# AMU_type_2_v1.net
KiCad netlist of a schematic drawn in Altium Designer
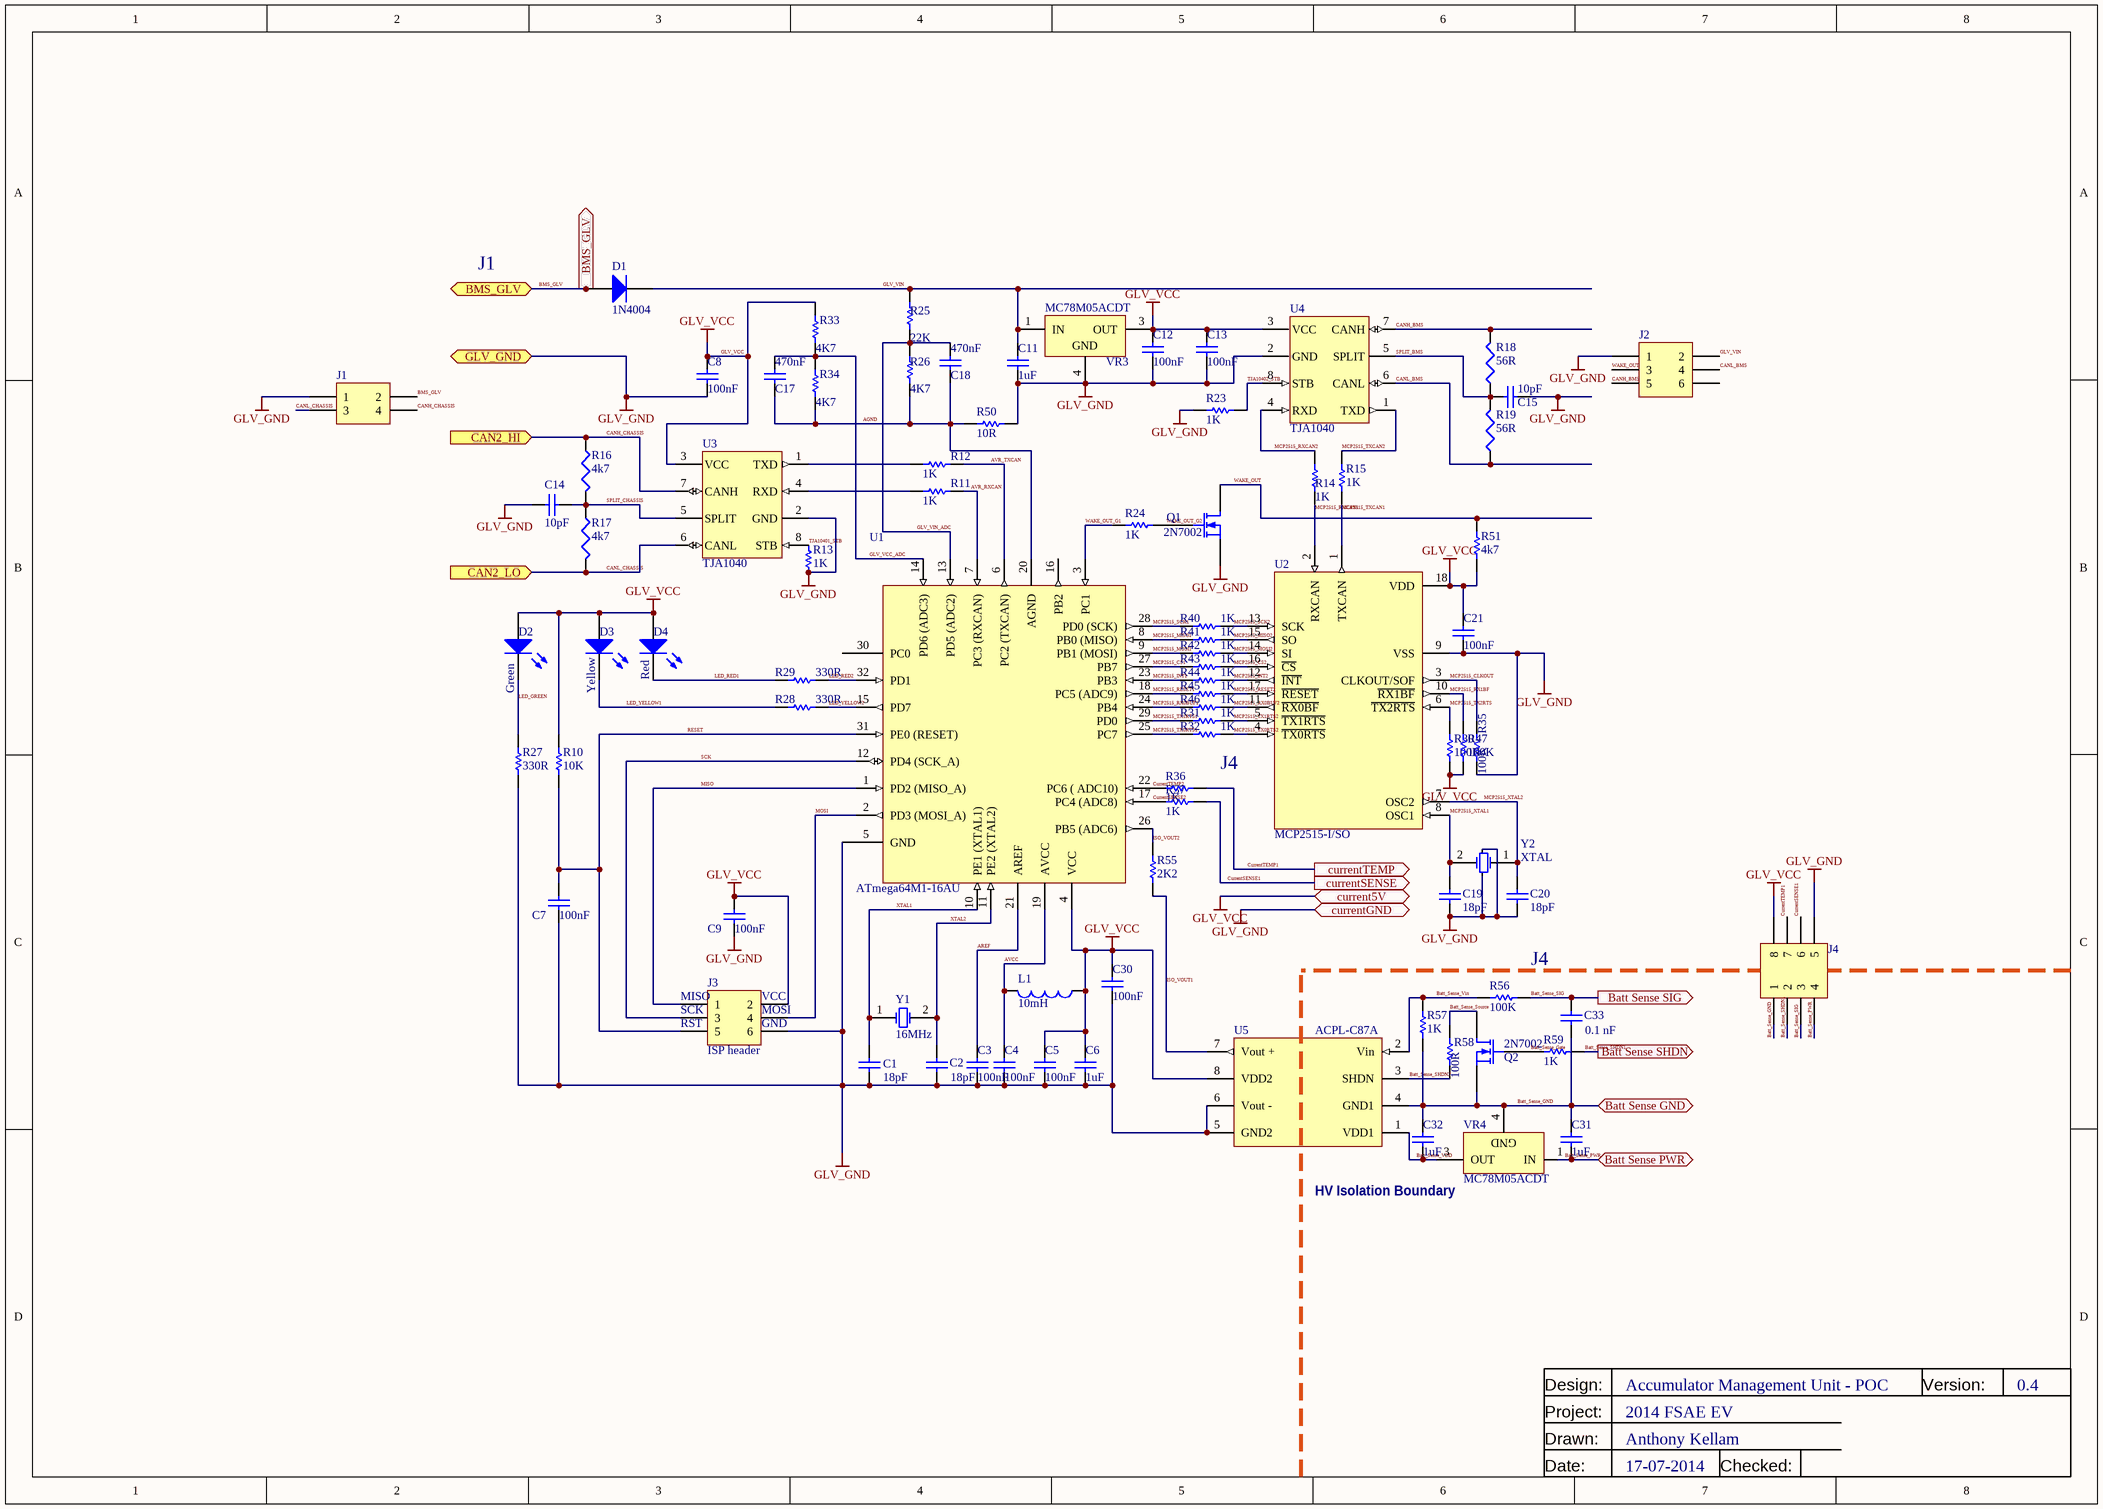
[diagram p0: AMU_type_2_v1.SchDoc]

(export (version "E")
  (design (tool "Eeschema 10.0.6"))
  (components
    (comp (ref "C1")
      (value "18pF")
      (footprint "0603C")
      (description "Capacitor (Semiconductor SIM Model)")
      (fields (field (name "Comment") "Cap Semi") (field (name "PUBLISHER") "Altium Limited"))
      (libsource (lib "Miscellaneous Devices") (part "Cap Semi"))
    )
    (comp (ref "C2")
      (value "18pF")
      (footprint "0603C")
      (description "Capacitor (Semiconductor SIM Model)")
      (fields (field (name "Comment") "Cap Semi") (field (name "PUBLISHER") "Altium Limited"))
      (libsource (lib "Miscellaneous Devices") (part "Cap Semi"))
    )
    (comp (ref "C3")
      (value "100nF")
      (footprint "0603C")
      (description "Capacitor (Semiconductor SIM Model)")
      (fields (field (name "Comment") "Cap Semi") (field (name "PUBLISHER") "Altium Limited"))
      (libsource (lib "Miscellaneous Devices") (part "Cap Semi"))
    )
    (comp (ref "C4")
      (value "100nF")
      (footprint "0603C")
      (description "Capacitor (Semiconductor SIM Model)")
      (fields (field (name "Comment") "Cap Semi") (field (name "PUBLISHER") "Altium Limited"))
      (libsource (lib "Miscellaneous Devices") (part "Cap Semi"))
    )
    (comp (ref "C5")
      (value "100nF")
      (footprint "0603C")
      (description "Capacitor (Semiconductor SIM Model)")
      (fields (field (name "Comment") "Cap Semi") (field (name "PUBLISHER") "Altium Limited"))
      (libsource (lib "Miscellaneous Devices") (part "Cap Semi"))
    )
    (comp (ref "C6")
      (value "1uF")
      (footprint "0603C")
      (description "Capacitor (Semiconductor SIM Model)")
      (fields (field (name "Comment") "Cap Semi") (field (name "PUBLISHER") "Altium Limited"))
      (libsource (lib "Miscellaneous Devices") (part "Cap Semi"))
    )
    (comp (ref "C7")
      (value "100nF")
      (footprint "0603C")
      (description "Capacitor (Semiconductor SIM Model)")
      (fields (field (name "Comment") "Cap Semi") (field (name "PUBLISHER") "Altium Limited"))
      (libsource (lib "Miscellaneous Devices") (part "Cap Semi"))
    )
    (comp (ref "C8")
      (value "100nF")
      (footprint "0603C")
      (description "Capacitor (Semiconductor SIM Model)")
      (fields (field (name "Comment") "Cap Semi") (field (name "PUBLISHER") "Altium Limited"))
      (libsource (lib "Miscellaneous Devices") (part "Cap Semi"))
    )
    (comp (ref "C9")
      (value "100nF")
      (footprint "0603C")
      (description "Capacitor (Semiconductor SIM Model)")
      (fields (field (name "Comment") "Cap Semi") (field (name "PUBLISHER") "Altium Limited"))
      (libsource (lib "Miscellaneous Devices") (part "Cap Semi"))
    )
    (comp (ref "C11")
      (value "1uF")
      (footprint "0603C")
      (description "Capacitor (Semiconductor SIM Model)")
      (fields (field (name "Comment") "Cap Semi") (field (name "PUBLISHER") "Altium Limited"))
      (libsource (lib "Miscellaneous Devices") (part "Cap Semi"))
    )
    (comp (ref "C12")
      (value "100nF")
      (footprint "0603C")
      (description "Capacitor (Semiconductor SIM Model)")
      (fields (field (name "Comment") "Cap Semi") (field (name "PUBLISHER") "Altium Limited"))
      (libsource (lib "Miscellaneous Devices") (part "Cap Semi"))
    )
    (comp (ref "C13")
      (value "100nF")
      (footprint "0603C")
      (description "Capacitor (Semiconductor SIM Model)")
      (fields (field (name "Comment") "Cap Semi") (field (name "PUBLISHER") "Altium Limited"))
      (libsource (lib "Miscellaneous Devices") (part "Cap Semi"))
    )
    (comp (ref "C14")
      (value "10pF")
      (footprint "0603C")
      (description "Capacitor (Semiconductor SIM Model)")
      (fields (field (name "Comment") "Cap Semi") (field (name "PUBLISHER") "Altium Limited"))
      (libsource (lib "Miscellaneous Devices") (part "Cap Semi"))
    )
    (comp (ref "C15")
      (value "10pF")
      (footprint "0603C")
      (description "Capacitor (Semiconductor SIM Model)")
      (fields (field (name "Comment") "Cap Semi") (field (name "PUBLISHER") "Altium Limited"))
      (libsource (lib "Miscellaneous Devices") (part "Cap Semi"))
    )
    (comp (ref "C17")
      (value "470nF")
      (footprint "0603C")
      (description "Capacitor (Semiconductor SIM Model)")
      (fields (field (name "Comment") "Cap Semi") (field (name "PUBLISHER") "Altium Limited"))
      (libsource (lib "Miscellaneous Devices") (part "Cap Semi"))
    )
    (comp (ref "C18")
      (value "470nF")
      (footprint "0603C")
      (description "Capacitor (Semiconductor SIM Model)")
      (fields (field (name "Comment") "Cap Semi") (field (name "PUBLISHER") "Altium Limited"))
      (libsource (lib "Miscellaneous Devices") (part "Cap Semi"))
    )
    (comp (ref "C19")
      (value "18pF")
      (footprint "0603C")
      (description "Capacitor (Semiconductor SIM Model)")
      (fields (field (name "Comment") "Cap Semi") (field (name "PUBLISHER") "Altium Limited"))
      (libsource (lib "Miscellaneous Devices") (part "Cap Semi"))
    )
    (comp (ref "C20")
      (value "18pF")
      (footprint "0603C")
      (description "Capacitor (Semiconductor SIM Model)")
      (fields (field (name "Comment") "Cap Semi") (field (name "PUBLISHER") "Altium Limited"))
      (libsource (lib "Miscellaneous Devices") (part "Cap Semi"))
    )
    (comp (ref "C21")
      (value "100nF")
      (footprint "0603C")
      (description "Capacitor (Semiconductor SIM Model)")
      (fields (field (name "Comment") "Cap Semi") (field (name "PUBLISHER") "Altium Limited"))
      (libsource (lib "Miscellaneous Devices") (part "Cap Semi"))
    )
    (comp (ref "C30")
      (value "100nF")
      (footprint "0603C")
      (description "Capacitor (Semiconductor SIM Model)")
      (fields (field (name "Comment") "Cap Semi") (field (name "PUBLISHER") "Altium Limited"))
      (libsource (lib "Miscellaneous Devices") (part "Cap Semi"))
    )
    (comp (ref "C31")
      (value "1uF")
      (footprint "0603C")
      (description "Capacitor (Semiconductor SIM Model)")
      (fields (field (name "Comment") "Cap Semi") (field (name "PUBLISHER") "Altium Limited"))
      (libsource (lib "Miscellaneous Devices") (part "Cap Semi"))
    )
    (comp (ref "C32")
      (value "1uF")
      (footprint "0603C")
      (description "Capacitor (Semiconductor SIM Model)")
      (fields (field (name "Comment") "Cap Semi") (field (name "PUBLISHER") "Altium Limited"))
      (libsource (lib "Miscellaneous Devices") (part "Cap Semi"))
    )
    (comp (ref "C33")
      (value "0.1 nF")
      (footprint "0603C")
      (description "Capacitor (Semiconductor SIM Model)")
      (fields (field (name "Comment") "Cap Semi") (field (name "PUBLISHER") "Altium Limited"))
      (libsource (lib "Miscellaneous Devices") (part "Cap Semi"))
    )
    (comp (ref "D1")
      (value "1N4004")
      (footprint "DO-214AC")
      (description "Default Diode")
      (fields (field (name "PUBLISHER") "Altium Limited"))
      (libsource (lib "Miscellaneous Devices") (part "Diode"))
    )
    (comp (ref "D2")
      (value "Green")
      (footprint "2012[0805]_LED")
      (description "Typical RED, GREEN, YELLOW, AMBER GaAs LED")
      (fields (field (name "PUBLISHER") "Altium Limited"))
      (libsource (lib "Miscellaneous Devices") (part "LED2"))
    )
    (comp (ref "D3")
      (value "Yellow")
      (footprint "2012[0805]_LED")
      (description "Typical RED, GREEN, YELLOW, AMBER GaAs LED")
      (fields (field (name "PUBLISHER") "Altium Limited"))
      (libsource (lib "Miscellaneous Devices") (part "LED2"))
    )
    (comp (ref "D4")
      (value "Red")
      (footprint "2012[0805]_LED")
      (description "Typical RED, GREEN, YELLOW, AMBER GaAs LED")
      (fields (field (name "PUBLISHER") "Altium Limited"))
      (libsource (lib "Miscellaneous Devices") (part "LED2"))
    )
    (comp (ref "J1")
      (value "Header 2X2")
      (footprint "Molex 4 Pin")
      (description "Header, 2-Pin, Dual row")
      (fields (field (name "PUBLISHER") "Altium Limited"))
      (libsource (lib "Miscellaneous Connectors") (part "Header 2X2"))
    )
    (comp (ref "J2")
      (value "Header 3X2")
      (footprint "Molex 6 Pin")
      (description "Header, 3-Pin, Dual row")
      (fields (field (name "PUBLISHER") "Altium Limited"))
      (libsource (lib "Miscellaneous Connectors") (part "Header 3X2"))
    )
    (comp (ref "J3")
      (value "ISP header")
      (footprint "ISP Header")
      (description "Header, 3-Pin, Dual row")
      (fields (field (name "PUBLISHER") "Altium Limited"))
      (libsource (lib "Miscellaneous Connectors") (part "Header 3X2"))
    )
    (comp (ref "J4")
      (value "Header 4X2")
      (footprint "MOLEX_8")
      (description "Header, 4-Pin, Dual row")
      (fields (field (name "PUBLISHER") "Altium Limited"))
      (libsource (lib "Miscellaneous Connectors") (part "Header 4X2"))
    )
    (comp (ref "L1")
      (value "10mH")
      (footprint "2012[0805]_IND")
      (description "Inductor")
      (fields (field (name "PUBLISHER") "Altium Limited"))
      (libsource (lib "Miscellaneous Devices") (part "Inductor"))
    )
    (comp (ref "Q1")
      (value "2N7002")
      (footprint "SOT23A")
      (description "N-Channel MOSFET")
      (fields
        (field (name "MANUFACTURER") "NXP Semiconductors")
        (field (name "MANUFACTURER PART NUMBER") "2N7002P,215")
        (field (name "PUBLISHER") "Altium Limited")
      )
      (libsource (lib "Miscellaneous Devices") (part "MOSFET-N"))
    )
    (comp (ref "Q2")
      (value "2N7002")
      (footprint "SOT23A")
      (description "N-Channel MOSFET")
      (fields (field (name "PUBLISHER") "Altium Limited"))
      (libsource (lib "") (part "MOSFET-N_1"))
    )
    (comp (ref "R10")
      (value "10K")
      (footprint "2012[0805]_Res")
      (description "Resistor")
      (fields (field (name "Comment") "Res1") (field (name "PUBLISHER") "Altium Limited"))
      (libsource (lib "Miscellaneous Devices") (part "Res1"))
    )
    (comp (ref "R11")
      (value "1K")
      (footprint "2012[0805]_Res")
      (description "Resistor")
      (fields (field (name "Comment") "Res1") (field (name "PUBLISHER") "Altium Limited"))
      (libsource (lib "Miscellaneous Devices") (part "Res1"))
    )
    (comp (ref "R12")
      (value "1K")
      (footprint "2012[0805]_Res")
      (description "Resistor")
      (fields (field (name "Comment") "Res1") (field (name "PUBLISHER") "Altium Limited"))
      (libsource (lib "Miscellaneous Devices") (part "Res1"))
    )
    (comp (ref "R13")
      (value "1K")
      (footprint "2012[0805]_Res")
      (description "Resistor")
      (fields (field (name "Comment") "Res1") (field (name "PUBLISHER") "Altium Limited"))
      (libsource (lib "") (part "Res1_1"))
    )
    (comp (ref "R14")
      (value "1K")
      (footprint "2012[0805]_Res")
      (description "Resistor")
      (fields (field (name "Comment") "Res1") (field (name "PUBLISHER") "Altium Limited"))
      (libsource (lib "Miscellaneous Devices") (part "Res1"))
    )
    (comp (ref "R15")
      (value "1K")
      (footprint "2012[0805]_Res")
      (description "Resistor")
      (fields (field (name "Comment") "Res1") (field (name "PUBLISHER") "Altium Limited"))
      (libsource (lib "Miscellaneous Devices") (part "Res1"))
    )
    (comp (ref "R16")
      (value "4k7")
      (footprint "2012[0805]_Res")
      (description "Resistor")
      (fields (field (name "Comment") "Res3") (field (name "PUBLISHER") "Altium Limited"))
      (libsource (lib "Miscellaneous Devices") (part "Res3"))
    )
    (comp (ref "R17")
      (value "4k7")
      (footprint "2012[0805]_Res")
      (description "Resistor")
      (fields (field (name "Comment") "Res3") (field (name "PUBLISHER") "Altium Limited"))
      (libsource (lib "Miscellaneous Devices") (part "Res3"))
    )
    (comp (ref "R18")
      (value "56R")
      (footprint "2012[0805]_Res")
      (description "Resistor")
      (fields (field (name "Comment") "Res3") (field (name "PUBLISHER") "Altium Limited"))
      (libsource (lib "Miscellaneous Devices") (part "Res3"))
    )
    (comp (ref "R19")
      (value "56R")
      (footprint "2012[0805]_Res")
      (description "Resistor")
      (fields (field (name "Comment") "Res3") (field (name "PUBLISHER") "Altium Limited"))
      (libsource (lib "Miscellaneous Devices") (part "Res3"))
    )
    (comp (ref "R23")
      (value "1K")
      (footprint "2012[0805]_Res")
      (description "Resistor")
      (fields (field (name "Comment") "Res1") (field (name "PUBLISHER") "Altium Limited"))
      (libsource (lib "Miscellaneous Devices") (part "Res1"))
    )
    (comp (ref "R24")
      (value "1K")
      (footprint "2012[0805]_Res")
      (description "Resistor")
      (fields (field (name "Comment") "Res1") (field (name "PUBLISHER") "Altium Limited"))
      (libsource (lib "Miscellaneous Devices") (part "Res1"))
    )
    (comp (ref "R25")
      (value "22K")
      (footprint "2012[0805]_Res")
      (description "Resistor")
      (fields (field (name "Comment") "Res1") (field (name "PUBLISHER") "Altium Limited"))
      (libsource (lib "Miscellaneous Devices") (part "Res1"))
    )
    (comp (ref "R26")
      (value "4K7")
      (footprint "2012[0805]_Res")
      (description "Resistor")
      (fields (field (name "Comment") "Res1") (field (name "PUBLISHER") "Altium Limited"))
      (libsource (lib "Miscellaneous Devices") (part "Res1"))
    )
    (comp (ref "R27")
      (value "330R")
      (footprint "2012[0805]_Res")
      (description "Resistor")
      (fields (field (name "Comment") "Res1") (field (name "PUBLISHER") "Altium Limited"))
      (libsource (lib "Miscellaneous Devices") (part "Res1"))
    )
    (comp (ref "R28")
      (value "330R")
      (footprint "2012[0805]_Res")
      (description "Resistor")
      (fields (field (name "Comment") "Res1") (field (name "PUBLISHER") "Altium Limited"))
      (libsource (lib "Miscellaneous Devices") (part "Res1"))
    )
    (comp (ref "R29")
      (value "330R")
      (footprint "2012[0805]_Res")
      (description "Resistor")
      (fields (field (name "Comment") "Res1") (field (name "PUBLISHER") "Altium Limited"))
      (libsource (lib "Miscellaneous Devices") (part "Res1"))
    )
    (comp (ref "R30")
      (value "100K")
      (footprint "2012[0805]_Res")
      (description "Resistor")
      (fields (field (name "Comment") "Res1") (field (name "PUBLISHER") "Altium Limited"))
      (libsource (lib "Miscellaneous Devices") (part "Res1"))
    )
    (comp (ref "R31")
      (value "1K")
      (footprint "2012[0805]_Res")
      (description "Resistor")
      (fields (field (name "Comment") "Res1") (field (name "PUBLISHER") "Altium Limited"))
      (libsource (lib "Miscellaneous Devices") (part "Res1"))
    )
    (comp (ref "R32")
      (value "1K")
      (footprint "2012[0805]_Res")
      (description "Resistor")
      (fields (field (name "Comment") "Res1") (field (name "PUBLISHER") "Altium Limited"))
      (libsource (lib "Miscellaneous Devices") (part "Res1"))
    )
    (comp (ref "R33")
      (value "4K7")
      (footprint "2012[0805]_Res")
      (description "Resistor")
      (fields (field (name "Comment") "Res1") (field (name "PUBLISHER") "Altium Limited"))
      (libsource (lib "Miscellaneous Devices") (part "Res1"))
    )
    (comp (ref "R34")
      (value "4K7")
      (footprint "2012[0805]_Res")
      (description "Resistor")
      (fields (field (name "Comment") "Res1") (field (name "PUBLISHER") "Altium Limited"))
      (libsource (lib "Miscellaneous Devices") (part "Res1"))
    )
    (comp (ref "R35")
      (value "100K")
      (footprint "2012[0805]_Res")
      (description "Resistor")
      (fields (field (name "Comment") "Res1") (field (name "PUBLISHER") "Altium Limited"))
      (libsource (lib "Miscellaneous Devices") (part "Res1"))
    )
    (comp (ref "R36")
      (value "1K")
      (footprint "2012[0805]_Res")
      (description "Resistor")
      (fields (field (name "Comment") "Res1") (field (name "PUBLISHER") "Altium Limited"))
      (libsource (lib "Miscellaneous Devices") (part "Res1"))
    )
    (comp (ref "R37")
      (value "1K")
      (footprint "2012[0805]_Res")
      (description "Resistor")
      (fields (field (name "Comment") "Res1") (field (name "PUBLISHER") "Altium Limited"))
      (libsource (lib "Miscellaneous Devices") (part "Res1"))
    )
    (comp (ref "R40")
      (value "1K")
      (footprint "2012[0805]_Res")
      (description "Resistor")
      (fields (field (name "Comment") "Res1") (field (name "PUBLISHER") "Altium Limited"))
      (libsource (lib "Miscellaneous Devices") (part "Res1"))
    )
    (comp (ref "R41")
      (value "1K")
      (footprint "2012[0805]_Res")
      (description "Resistor")
      (fields (field (name "Comment") "Res1") (field (name "PUBLISHER") "Altium Limited"))
      (libsource (lib "Miscellaneous Devices") (part "Res1"))
    )
    (comp (ref "R42")
      (value "1K")
      (footprint "2012[0805]_Res")
      (description "Resistor")
      (fields (field (name "Comment") "Res1") (field (name "PUBLISHER") "Altium Limited"))
      (libsource (lib "Miscellaneous Devices") (part "Res1"))
    )
    (comp (ref "R43")
      (value "1K")
      (footprint "2012[0805]_Res")
      (description "Resistor")
      (fields (field (name "Comment") "Res1") (field (name "PUBLISHER") "Altium Limited"))
      (libsource (lib "Miscellaneous Devices") (part "Res1"))
    )
    (comp (ref "R44")
      (value "1K")
      (footprint "2012[0805]_Res")
      (description "Resistor")
      (fields (field (name "Comment") "Res1") (field (name "PUBLISHER") "Altium Limited"))
      (libsource (lib "Miscellaneous Devices") (part "Res1"))
    )
    (comp (ref "R45")
      (value "1K")
      (footprint "2012[0805]_Res")
      (description "Resistor")
      (fields (field (name "Comment") "Res1") (field (name "PUBLISHER") "Altium Limited"))
      (libsource (lib "Miscellaneous Devices") (part "Res1"))
    )
    (comp (ref "R46")
      (value "1K")
      (footprint "2012[0805]_Res")
      (description "Resistor")
      (fields (field (name "Comment") "Res1") (field (name "PUBLISHER") "Altium Limited"))
      (libsource (lib "Miscellaneous Devices") (part "Res1"))
    )
    (comp (ref "R47")
      (value "100K")
      (footprint "2012[0805]_Res")
      (description "Resistor")
      (fields (field (name "Comment") "Res1") (field (name "PUBLISHER") "Altium Limited"))
      (libsource (lib "Miscellaneous Devices") (part "Res1"))
    )
    (comp (ref "R50")
      (value "10R")
      (footprint "2012[0805]_Res")
      (description "Resistor")
      (fields (field (name "Comment") "Res1") (field (name "PUBLISHER") "Altium Limited"))
      (libsource (lib "Miscellaneous Devices") (part "Res1"))
    )
    (comp (ref "R51")
      (value "4k7")
      (footprint "2012[0805]_Res")
      (description "Resistor")
      (fields (field (name "Comment") "Res1") (field (name "PUBLISHER") "Altium Limited"))
      (libsource (lib "Miscellaneous Devices") (part "Res1"))
    )
    (comp (ref "R55")
      (value "2K2")
      (footprint "2012[0805]_Res")
      (description "Resistor")
      (fields (field (name "Comment") "Res1") (field (name "PUBLISHER") "Altium Limited"))
      (libsource (lib "Miscellaneous Devices") (part "Res1"))
    )
    (comp (ref "R56")
      (value "100K")
      (footprint "2012[0805]_Res")
      (description "Resistor")
      (fields (field (name "Comment") "Res1") (field (name "PUBLISHER") "Altium Limited"))
      (libsource (lib "Miscellaneous Devices") (part "Res1"))
    )
    (comp (ref "R57")
      (value "1K")
      (footprint "2012[0805]_Res")
      (description "Resistor")
      (fields (field (name "Comment") "Res1") (field (name "PUBLISHER") "Altium Limited"))
      (libsource (lib "Miscellaneous Devices") (part "Res1"))
    )
    (comp (ref "R58")
      (value "100R")
      (footprint "2012[0805]_Res")
      (description "Resistor")
      (fields (field (name "Comment") "Res1") (field (name "PUBLISHER") "Altium Limited"))
      (libsource (lib "Miscellaneous Devices") (part "Res1"))
    )
    (comp (ref "R59")
      (value "1K")
      (footprint "2012[0805]_Res")
      (description "Resistor")
      (fields (field (name "Comment") "Res1") (field (name "PUBLISHER") "Altium Limited"))
      (libsource (lib "Miscellaneous Devices") (part "Res1"))
    )
    (comp (ref "U1")
      (value "ATmega64M1-16AU")
      (footprint "32A_L")
      (description "8-Bit AVR Microcontroller with 8K Bytes of In-System Programmable Flash Memory")
      (fields (field (name "PUBLISHER") "Altium Limited"))
      (libsource (lib "Atmel Microcontroller 8-Bit AVR") (part "ATmega8-16AC"))
    )
    (comp (ref "U2")
      (value "MCP2515-I/SO")
      (footprint "SOIC-SO18_N")
      (description "Stand-Alone CAN Controller With SPI Interface, 18-Pin SOIC, Industrial Temperature")
      (fields (field (name "PUBLISHER") "Altium Limited"))
      (libsource (lib "Microchip Interface") (part "MCP2515-I/SO"))
    )
    (comp (ref "U3")
      (value "TJA1040")
      (footprint "Miscellaneous Devices:SO8_L")
      (libsource (lib "Schlib1") (part "TJA1040"))
    )
    (comp (ref "U4")
      (value "TJA1040")
      (footprint "Miscellaneous Devices:SO8_L")
      (libsource (lib "") (part "TJA1040_1"))
    )
    (comp (ref "U5")
      (value "ACPL-C87A")
      (footprint "8S2_L")
      (description "Isolated CAN transceiver")
      (fields (field (name "PUBLISHER") "Altium Limited"))
      (libsource (lib "Atmel Microcontroller 8-Bit AVR") (part "AT90S2343-10SI"))
    )
    (comp (ref "VR3")
      (value "MC78M05ACDT")
      (footprint "369A-13")
      (description "Three-Terminal Medium Current Positive Voltage Regulator")
      (fields (field (name "PUBLISHER") "Altium Limited"))
      (libsource (lib "ON Semi Power Mgt Voltage Regulator") (part "MC78M05ACDT"))
    )
    (comp (ref "VR4")
      (value "MC78M05ACDT")
      (footprint "369A-13")
      (description "Three-Terminal Medium Current Positive Voltage Regulator")
      (fields (field (name "PUBLISHER") "Altium Limited"))
      (libsource (lib "") (part "MC78M05ACDT_1"))
    )
    (comp (ref "Y1")
      (value "16MHz")
      (footprint "Crystal")
      (description "Crystal Oscillator")
      (fields (field (name "PUBLISHER") "Altium Limited"))
      (libsource (lib "Miscellaneous Devices") (part "XTAL"))
    )
    (comp (ref "Y2")
      (value "XTAL")
      (footprint "MCP2515_XTAL")
      (description "Crystal Oscillator")
      (fields (field (name "PUBLISHER") "Altium Limited"))
      (libsource (lib "Schlib1") (part "XTAL"))
    )
  )
  (nets
    (net (code "1") (name "/AGND") (class "Default")
      (node (ref "C17") (pin "1") (pinfunction "1_1") (pintype "passive"))
      (node (ref "C18") (pin "1") (pinfunction "1_1") (pintype "passive"))
      (node (ref "R26") (pin "2") (pinfunction "2_2") (pintype "passive"))
      (node (ref "R34") (pin "2") (pinfunction "2_2") (pintype "passive"))
      (node (ref "R50") (pin "1") (pinfunction "1_1") (pintype "passive"))
      (node (ref "U1") (pin "20") (pinfunction "AGND_20") (pintype "power_in"))
    )
    (net (code "2") (name "/AREF") (class "Default")
      (node (ref "C3") (pin "1") (pinfunction "1_1") (pintype "passive"))
      (node (ref "U1") (pin "21") (pinfunction "AREF_21") (pintype "power_in"))
    )
    (net (code "3") (name "/AVCC") (class "Default")
      (node (ref "C4") (pin "1") (pinfunction "1_1") (pintype "passive"))
      (node (ref "L1") (pin "2") (pinfunction "2_2") (pintype "passive"))
      (node (ref "U1") (pin "19") (pinfunction "AVCC_19") (pintype "power_in"))
    )
    (net (code "4") (name "/AVR_RXCAN") (class "Default")
      (node (ref "R11") (pin "2") (pinfunction "2_2") (pintype "passive"))
      (node (ref "U1") (pin "7") (pinfunction "PC3_(RXCAN)_7") (pintype "input"))
    )
    (net (code "5") (name "/AVR_TXCAN") (class "Default")
      (node (ref "R12") (pin "1") (pinfunction "1_1") (pintype "passive"))
      (node (ref "U1") (pin "6") (pinfunction "PC2_(TXCAN)_6") (pintype "output"))
    )
    (net (code "6") (name "/BMS_GLV") (class "Default")
      (node (ref "D1") (pin "1") (pinfunction "A_1") (pintype "passive"))
      (node (ref "J1") (pin "2") (pinfunction "2_2") (pintype "passive"))
    )
    (net (code "7") (name "/Batt_Sense_GND") (class "Default")
      (node (ref "C31") (pin "2") (pinfunction "2_2") (pintype "passive"))
      (node (ref "C32") (pin "2") (pinfunction "2_2") (pintype "passive"))
      (node (ref "C33") (pin "1") (pinfunction "1_1") (pintype "passive"))
      (node (ref "J4") (pin "1") (pinfunction "1_1") (pintype "passive"))
      (node (ref "Q2") (pin "2") (pinfunction "S_2") (pintype "passive"))
      (node (ref "R57") (pin "1") (pinfunction "1_1") (pintype "passive"))
      (node (ref "U5") (pin "4") (pinfunction "GND1_4") (pintype "power_in"))
      (node (ref "VR4") (pin "4") (pinfunction "GND_4") (pintype "power_in"))
    )
    (net (code "8") (name "/Batt_Sense_Gate") (class "Default")
      (node (ref "Q2") (pin "1") (pinfunction "G_1") (pintype "passive"))
      (node (ref "R59") (pin "2") (pinfunction "2_2") (pintype "passive"))
    )
    (net (code "9") (name "/Batt_Sense_PWR") (class "Default")
      (node (ref "C31") (pin "1") (pinfunction "1_1") (pintype "passive"))
      (node (ref "J4") (pin "4") (pinfunction "4_4") (pintype "passive"))
      (node (ref "VR4") (pin "1") (pinfunction "IN_1") (pintype "power_in"))
    )
    (net (code "10") (name "/Batt_Sense_SHDN1") (class "Default")
      (node (ref "J4") (pin "2") (pinfunction "2_2") (pintype "passive"))
      (node (ref "R59") (pin "1") (pinfunction "1_1") (pintype "passive"))
    )
    (net (code "11") (name "/Batt_Sense_SHDN2") (class "Default")
      (node (ref "R58") (pin "1") (pinfunction "1_1") (pintype "passive"))
      (node (ref "U5") (pin "3") (pinfunction "SHDN_3") (pintype "open_collector"))
    )
    (net (code "12") (name "/Batt_Sense_SIG") (class "Default")
      (node (ref "C33") (pin "2") (pinfunction "2_2") (pintype "passive"))
      (node (ref "J4") (pin "3") (pinfunction "3_3") (pintype "passive"))
      (node (ref "R56") (pin "1") (pinfunction "1_1") (pintype "passive"))
    )
    (net (code "13") (name "/Batt_Sense_Source") (class "Default")
      (node (ref "Q2") (pin "3") (pinfunction "D_3") (pintype "passive"))
      (node (ref "R58") (pin "2") (pinfunction "2_2") (pintype "passive"))
    )
    (net (code "14") (name "/Batt_Sense_VDD") (class "Default")
      (node (ref "C32") (pin "1") (pinfunction "1_1") (pintype "passive"))
      (node (ref "U5") (pin "1") (pinfunction "VDD1_1") (pintype "power_in"))
      (node (ref "VR4") (pin "3") (pinfunction "OUT_3") (pintype "power_in"))
    )
    (net (code "15") (name "/Batt_Sense_Vin") (class "Default")
      (node (ref "R56") (pin "2") (pinfunction "2_2") (pintype "passive"))
      (node (ref "R57") (pin "2") (pinfunction "2_2") (pintype "passive"))
      (node (ref "U5") (pin "2") (pinfunction "Vin_2") (pintype "input"))
    )
    (net (code "16") (name "/CANH_BMS") (class "Default")
      (node (ref "J2") (pin "5") (pinfunction "5_5") (pintype "passive"))
      (node (ref "R18") (pin "2") (pinfunction "2_2") (pintype "passive"))
      (node (ref "U4") (pin "7") (pinfunction "CANH_7") (pintype "bidirectional"))
    )
    (net (code "17") (name "/CANH_CHASSIS") (class "Default")
      (node (ref "J1") (pin "4") (pinfunction "4_4") (pintype "passive"))
      (node (ref "R16") (pin "1") (pinfunction "1_1") (pintype "passive"))
      (node (ref "U3") (pin "7") (pinfunction "CANH_7") (pintype "bidirectional"))
    )
    (net (code "18") (name "/CANL_BMS") (class "Default")
      (node (ref "J2") (pin "4") (pinfunction "4_4") (pintype "passive"))
      (node (ref "R19") (pin "1") (pinfunction "1_1") (pintype "passive"))
      (node (ref "U4") (pin "6") (pinfunction "CANL_6") (pintype "bidirectional"))
    )
    (net (code "19") (name "/CANL_CHASSIS") (class "Default")
      (node (ref "J1") (pin "3") (pinfunction "3_3") (pintype "passive"))
      (node (ref "R17") (pin "2") (pinfunction "2_2") (pintype "passive"))
      (node (ref "U3") (pin "6") (pinfunction "CANL_6") (pintype "bidirectional"))
    )
    (net (code "20") (name "/CurrentSENSE1") (class "Default")
      (node (ref "J4") (pin "6") (pinfunction "6_6") (pintype "passive"))
      (node (ref "R37") (pin "1") (pinfunction "1_1") (pintype "passive"))
    )
    (net (code "21") (name "/CurrentSENSE2") (class "Default")
      (node (ref "R37") (pin "2") (pinfunction "2_2") (pintype "passive"))
      (node (ref "U1") (pin "17") (pinfunction "PC4_(ADC8)_17") (pintype "input"))
    )
    (net (code "22") (name "/CurrentTEMP1") (class "Default")
      (node (ref "J4") (pin "7") (pinfunction "7_7") (pintype "passive"))
      (node (ref "R36") (pin "1") (pinfunction "1_1") (pintype "passive"))
    )
    (net (code "23") (name "/CurrentTEMP2") (class "Default")
      (node (ref "R36") (pin "2") (pinfunction "2_2") (pintype "passive"))
      (node (ref "U1") (pin "22") (pinfunction "PC6_(_ADC10)_22") (pintype "input"))
    )
    (net (code "24") (name "/GLV_VCC_ADC") (class "Default")
      (node (ref "C17") (pin "2") (pinfunction "2_2") (pintype "passive"))
      (node (ref "R33") (pin "2") (pinfunction "2_2") (pintype "passive"))
      (node (ref "R34") (pin "1") (pinfunction "1_1") (pintype "passive"))
      (node (ref "U1") (pin "14") (pinfunction "PD6_(ADC3)_14") (pintype "input"))
    )
    (net (code "25") (name "/GLV_VIN") (class "Default")
      (node (ref "C11") (pin "2") (pinfunction "2_2") (pintype "passive"))
      (node (ref "D1") (pin "2") (pinfunction "K_2") (pintype "passive"))
      (node (ref "J2") (pin "2") (pinfunction "2_2") (pintype "passive"))
      (node (ref "R25") (pin "1") (pinfunction "1_1") (pintype "passive"))
      (node (ref "VR3") (pin "1") (pinfunction "IN_1") (pintype "power_in"))
    )
    (net (code "26") (name "/GLV_VIN_ADC") (class "Default")
      (node (ref "C18") (pin "2") (pinfunction "2_2") (pintype "passive"))
      (node (ref "R25") (pin "2") (pinfunction "2_2") (pintype "passive"))
      (node (ref "R26") (pin "1") (pinfunction "1_1") (pintype "passive"))
      (node (ref "U1") (pin "13") (pinfunction "PD5_(ADC2)_13") (pintype "input"))
    )
    (net (code "27") (name "/ISO_VOUT1") (class "Default")
      (node (ref "R55") (pin "2") (pinfunction "2_2") (pintype "passive"))
      (node (ref "U5") (pin "7") (pinfunction "Vout_+_7") (pintype "output"))
    )
    (net (code "28") (name "/ISO_VOUT2") (class "Default")
      (node (ref "R55") (pin "1") (pinfunction "1_1") (pintype "passive"))
      (node (ref "U1") (pin "26") (pinfunction "PB5_(ADC6)_26") (pintype "output"))
    )
    (net (code "29") (name "/LED_GREEN") (class "Default")
      (node (ref "D2") (pin "2") (pinfunction "K_2") (pintype "passive"))
      (node (ref "R27") (pin "2") (pinfunction "2_2") (pintype "passive"))
    )
    (net (code "30") (name "/LED_RED1") (class "Default")
      (node (ref "D4") (pin "2") (pinfunction "K_2") (pintype "passive"))
      (node (ref "R29") (pin "1") (pinfunction "1_1") (pintype "passive"))
    )
    (net (code "31") (name "/LED_RED2") (class "Default")
      (node (ref "R29") (pin "2") (pinfunction "2_2") (pintype "passive"))
      (node (ref "U1") (pin "32") (pinfunction "PD1_32") (pintype "input"))
    )
    (net (code "32") (name "/LED_YELLOW1") (class "Default")
      (node (ref "D3") (pin "2") (pinfunction "K_2") (pintype "passive"))
      (node (ref "R28") (pin "1") (pinfunction "1_1") (pintype "passive"))
    )
    (net (code "33") (name "/LED_YELLOW2") (class "Default")
      (node (ref "R28") (pin "2") (pinfunction "2_2") (pintype "passive"))
      (node (ref "U1") (pin "15") (pinfunction "PD7_15") (pintype "output"))
    )
    (net (code "34") (name "/MCP2515_CLKOUT") (class "Default")
      (node (ref "R35") (pin "1") (pinfunction "1_1") (pintype "passive"))
      (node (ref "U2") (pin "3") (pinfunction "CLKOUT/SOF_3") (pintype "output"))
    )
    (net (code "35") (name "/MCP2515_CS1") (class "Default")
      (node (ref "R43") (pin "1") (pinfunction "1_1") (pintype "passive"))
      (node (ref "U1") (pin "27") (pinfunction "PB7_27") (pintype "output"))
    )
    (net (code "36") (name "/MCP2515_CS2") (class "Default")
      (node (ref "R43") (pin "2") (pinfunction "2_2") (pintype "passive"))
      (node (ref "U2") (pin "16") (pinfunction "~{CS}_16") (pintype "input"))
    )
    (net (code "37") (name "/MCP2515_INT1") (class "Default")
      (node (ref "R44") (pin "1") (pinfunction "1_1") (pintype "passive"))
      (node (ref "U1") (pin "23") (pinfunction "PB3_23") (pintype "input"))
    )
    (net (code "38") (name "/MCP2515_INT2") (class "Default")
      (node (ref "R44") (pin "2") (pinfunction "2_2") (pintype "passive"))
      (node (ref "U2") (pin "12") (pinfunction "~{INT}_12") (pintype "output"))
    )
    (net (code "39") (name "/MCP2515_MISO1") (class "Default")
      (node (ref "R41") (pin "1") (pinfunction "1_1") (pintype "passive"))
      (node (ref "U1") (pin "8") (pinfunction "PB0_(MISO)_8") (pintype "input"))
    )
    (net (code "40") (name "/MCP2515_MISO2") (class "Default")
      (node (ref "R41") (pin "2") (pinfunction "2_2") (pintype "passive"))
      (node (ref "U2") (pin "15") (pinfunction "SO_15") (pintype "output"))
    )
    (net (code "41") (name "/MCP2515_MOSI1") (class "Default")
      (node (ref "R42") (pin "1") (pinfunction "1_1") (pintype "passive"))
      (node (ref "U1") (pin "9") (pinfunction "PB1_(MOSI)_9") (pintype "output"))
    )
    (net (code "42") (name "/MCP2515_MOSI2") (class "Default")
      (node (ref "R42") (pin "2") (pinfunction "2_2") (pintype "passive"))
      (node (ref "U2") (pin "14") (pinfunction "SI_14") (pintype "input"))
    )
    (net (code "43") (name "/MCP2515_RESET1") (class "Default")
      (node (ref "R45") (pin "1") (pinfunction "1_1") (pintype "passive"))
      (node (ref "U1") (pin "18") (pinfunction "PC5_(ADC9)_18") (pintype "output"))
    )
    (net (code "44") (name "/MCP2515_RESET2") (class "Default")
      (node (ref "R45") (pin "2") (pinfunction "2_2") (pintype "passive"))
      (node (ref "U2") (pin "17") (pinfunction "~{RESET}_17") (pintype "input"))
    )
    (net (code "45") (name "/MCP2515_RX0BUF1") (class "Default")
      (node (ref "R46") (pin "1") (pinfunction "1_1") (pintype "passive"))
      (node (ref "U1") (pin "24") (pinfunction "PB4_24") (pintype "input"))
    )
    (net (code "46") (name "/MCP2515_RX0BUF2") (class "Default")
      (node (ref "R46") (pin "2") (pinfunction "2_2") (pintype "passive"))
      (node (ref "U2") (pin "11") (pinfunction "~{RX0BF}_11") (pintype "output"))
    )
    (net (code "47") (name "/MCP2515_RX1BF") (class "Default")
      (node (ref "R47") (pin "2") (pinfunction "2_2") (pintype "passive"))
      (node (ref "U2") (pin "10") (pinfunction "~{RX1BF}_10") (pintype "output"))
    )
    (net (code "48") (name "/MCP2515_RXCAN1") (class "Default")
      (node (ref "R14") (pin "2") (pinfunction "2_2") (pintype "passive"))
      (node (ref "U2") (pin "2") (pinfunction "RXCAN_2") (pintype "input"))
    )
    (net (code "49") (name "/MCP2515_RXCAN2") (class "Default")
      (node (ref "R14") (pin "1") (pinfunction "1_1") (pintype "passive"))
      (node (ref "U4") (pin "4") (pinfunction "RXD_4") (pintype "input"))
    )
    (net (code "50") (name "/MCP2515_SCK1") (class "Default")
      (node (ref "R40") (pin "1") (pinfunction "1_1") (pintype "passive"))
      (node (ref "U1") (pin "28") (pinfunction "PD0_(SCK)_28") (pintype "output"))
    )
    (net (code "51") (name "/MCP2515_SCK2") (class "Default")
      (node (ref "R40") (pin "2") (pinfunction "2_2") (pintype "passive"))
      (node (ref "U2") (pin "13") (pinfunction "SCK_13") (pintype "input"))
    )
    (net (code "52") (name "/MCP2515_TX0RTS1") (class "Default")
      (node (ref "R32") (pin "1") (pinfunction "1_1") (pintype "passive"))
      (node (ref "U1") (pin "25") (pinfunction "PC7_25") (pintype "output"))
    )
    (net (code "53") (name "/MCP2515_TX0RTS2") (class "Default")
      (node (ref "R32") (pin "2") (pinfunction "2_2") (pintype "passive"))
      (node (ref "U2") (pin "4") (pinfunction "~{TX0RTS}_4") (pintype "input"))
    )
    (net (code "54") (name "/MCP2515_TX1RTS1") (class "Default")
      (node (ref "R31") (pin "1") (pinfunction "1_1") (pintype "passive"))
      (node (ref "U1") (pin "29") (pinfunction "PD0_29") (pintype "output"))
    )
    (net (code "55") (name "/MCP2515_TX1RTS2") (class "Default")
      (node (ref "R31") (pin "2") (pinfunction "2_2") (pintype "passive"))
      (node (ref "U2") (pin "5") (pinfunction "~{TX1RTS}_5") (pintype "input"))
    )
    (net (code "56") (name "/MCP2515_TX2RTS") (class "Default")
      (node (ref "R30") (pin "2") (pinfunction "2_2") (pintype "passive"))
      (node (ref "U2") (pin "6") (pinfunction "~{TX2RTS}_6") (pintype "input"))
    )
    (net (code "57") (name "/MCP2515_TXCAN1") (class "Default")
      (node (ref "R15") (pin "2") (pinfunction "2_2") (pintype "passive"))
      (node (ref "U2") (pin "1") (pinfunction "TXCAN_1") (pintype "output"))
    )
    (net (code "58") (name "/MCP2515_TXCAN2") (class "Default")
      (node (ref "R15") (pin "1") (pinfunction "1_1") (pintype "passive"))
      (node (ref "U4") (pin "1") (pinfunction "TXD_1") (pintype "output"))
    )
    (net (code "59") (name "/MCP2515_XTAL1") (class "Default")
      (node (ref "C19") (pin "1") (pinfunction "1_1") (pintype "passive"))
      (node (ref "U2") (pin "8") (pinfunction "OSC1_8") (pintype "input"))
      (node (ref "Y2") (pin "2") (pinfunction "OSC2_2") (pintype "passive"))
    )
    (net (code "60") (name "/MCP2515_XTAL2") (class "Default")
      (node (ref "C20") (pin "2") (pinfunction "2_2") (pintype "passive"))
      (node (ref "U2") (pin "7") (pinfunction "OSC2_7") (pintype "output"))
      (node (ref "Y2") (pin "1") (pinfunction "OSC1_1") (pintype "passive"))
    )
    (net (code "61") (name "/MISO") (class "Default")
      (node (ref "J3") (pin "1") (pinfunction "1_1") (pintype "passive"))
      (node (ref "U1") (pin "1") (pinfunction "PD2_(MISO_A)_1") (pintype "input"))
    )
    (net (code "62") (name "/MOSI") (class "Default")
      (node (ref "J3") (pin "4") (pinfunction "4_4") (pintype "passive"))
      (node (ref "U1") (pin "2") (pinfunction "PD3_(MOSI_A)_2") (pintype "output"))
    )
    (net (code "63") (name "/RESET") (class "Default")
      (node (ref "C7") (pin "2") (pinfunction "2_2") (pintype "passive"))
      (node (ref "J3") (pin "5") (pinfunction "5_5") (pintype "passive"))
      (node (ref "R10") (pin "1") (pinfunction "1_1") (pintype "passive"))
      (node (ref "U1") (pin "31") (pinfunction "PE0_(RESET)_31") (pintype "input"))
    )
    (net (code "64") (name "/SCK") (class "Default")
      (node (ref "J3") (pin "3") (pinfunction "3_3") (pintype "passive"))
      (node (ref "U1") (pin "12") (pinfunction "PD4_(SCK_A)_12") (pintype "bidirectional"))
    )
    (net (code "65") (name "/SPLIT_BMS") (class "Default")
      (node (ref "C15") (pin "2") (pinfunction "2_2") (pintype "passive"))
      (node (ref "R18") (pin "1") (pinfunction "1_1") (pintype "passive"))
      (node (ref "R19") (pin "2") (pinfunction "2_2") (pintype "passive"))
      (node (ref "U4") (pin "5") (pinfunction "SPLIT_5") (pintype "power_in"))
    )
    (net (code "66") (name "/SPLIT_CHASSIS") (class "Default")
      (node (ref "C14") (pin "2") (pinfunction "2_2") (pintype "passive"))
      (node (ref "R16") (pin "2") (pinfunction "2_2") (pintype "passive"))
      (node (ref "R17") (pin "1") (pinfunction "1_1") (pintype "passive"))
      (node (ref "U3") (pin "5") (pinfunction "SPLIT_5") (pintype "power_in"))
    )
    (net (code "67") (name "/TJA10401_STB") (class "Default")
      (node (ref "R13") (pin "2") (pinfunction "2_2") (pintype "passive"))
      (node (ref "U3") (pin "8") (pinfunction "STB_8") (pintype "input"))
    )
    (net (code "68") (name "/TJA10402_STB") (class "Default")
      (node (ref "R23") (pin "2") (pinfunction "2_2") (pintype "passive"))
      (node (ref "U4") (pin "8") (pinfunction "STB_8") (pintype "input"))
    )
    (net (code "69") (name "/WAKE_OUT") (class "Default")
      (node (ref "J2") (pin "3") (pinfunction "3_3") (pintype "passive"))
      (node (ref "Q1") (pin "3") (pinfunction "D_3") (pintype "passive"))
      (node (ref "R51") (pin "2") (pinfunction "2_2") (pintype "passive"))
    )
    (net (code "70") (name "/WAKE_OUT_G1") (class "Default")
      (node (ref "R24") (pin "1") (pinfunction "1_1") (pintype "passive"))
      (node (ref "U1") (pin "3") (pinfunction "PC1_3") (pintype "input"))
    )
    (net (code "71") (name "/WAKE_OUT_G2") (class "Default")
      (node (ref "Q1") (pin "1") (pinfunction "G_1") (pintype "passive"))
      (node (ref "R24") (pin "2") (pinfunction "2_2") (pintype "passive"))
    )
    (net (code "72") (name "/XTAL1") (class "Default")
      (node (ref "C1") (pin "2") (pinfunction "2_2") (pintype "passive"))
      (node (ref "U1") (pin "10") (pinfunction "PE1_(XTAL1)_10") (pintype "input"))
      (node (ref "Y1") (pin "1") (pinfunction "OSC1_1") (pintype "passive"))
    )
    (net (code "73") (name "/XTAL2") (class "Default")
      (node (ref "C2") (pin "2") (pinfunction "2_2") (pintype "passive"))
      (node (ref "U1") (pin "11") (pinfunction "PE2_(XTAL2)_11") (pintype "input"))
      (node (ref "Y1") (pin "2") (pinfunction "OSC2_2") (pintype "passive"))
    )
    (net (code "74") (name "GLV_GND") (class "Default")
      (node (ref "C1") (pin "1") (pinfunction "1_1") (pintype "passive"))
      (node (ref "C11") (pin "1") (pinfunction "1_1") (pintype "passive"))
      (node (ref "C12") (pin "1") (pinfunction "1_1") (pintype "passive"))
      (node (ref "C13") (pin "1") (pinfunction "1_1") (pintype "passive"))
      (node (ref "C14") (pin "1") (pinfunction "1_1") (pintype "passive"))
      (node (ref "C15") (pin "1") (pinfunction "1_1") (pintype "passive"))
      (node (ref "C19") (pin "2") (pinfunction "2_2") (pintype "passive"))
      (node (ref "C2") (pin "1") (pinfunction "1_1") (pintype "passive"))
      (node (ref "C20") (pin "1") (pinfunction "1_1") (pintype "passive"))
      (node (ref "C21") (pin "1") (pinfunction "1_1") (pintype "passive"))
      (node (ref "C3") (pin "2") (pinfunction "2_2") (pintype "passive"))
      (node (ref "C30") (pin "2") (pinfunction "2_2") (pintype "passive"))
      (node (ref "C4") (pin "2") (pinfunction "2_2") (pintype "passive"))
      (node (ref "C5") (pin "2") (pinfunction "2_2") (pintype "passive"))
      (node (ref "C6") (pin "2") (pinfunction "2_2") (pintype "passive"))
      (node (ref "C7") (pin "1") (pinfunction "1_1") (pintype "passive"))
      (node (ref "C8") (pin "1") (pinfunction "1_1") (pintype "passive"))
      (node (ref "C9") (pin "1") (pinfunction "1_1") (pintype "passive"))
      (node (ref "J1") (pin "1") (pinfunction "1_1") (pintype "passive"))
      (node (ref "J2") (pin "1") (pinfunction "1_1") (pintype "passive"))
      (node (ref "J3") (pin "6") (pinfunction "6_6") (pintype "passive"))
      (node (ref "J4") (pin "5") (pinfunction "5_5") (pintype "passive"))
      (node (ref "Q1") (pin "2") (pinfunction "S_2") (pintype "passive"))
      (node (ref "R13") (pin "1") (pinfunction "1_1") (pintype "passive"))
      (node (ref "R23") (pin "1") (pinfunction "1_1") (pintype "passive"))
      (node (ref "R27") (pin "1") (pinfunction "1_1") (pintype "passive"))
      (node (ref "R35") (pin "2") (pinfunction "2_2") (pintype "passive"))
      (node (ref "R50") (pin "2") (pinfunction "2_2") (pintype "passive"))
      (node (ref "U1") (pin "5") (pinfunction "GND_5") (pintype "power_in"))
      (node (ref "U2") (pin "9") (pinfunction "VSS_9") (pintype "power_in"))
      (node (ref "U3") (pin "2") (pinfunction "GND_2") (pintype "power_in"))
      (node (ref "U4") (pin "2") (pinfunction "GND_2") (pintype "power_in"))
      (node (ref "U5") (pin "5") (pinfunction "GND2_5") (pintype "power_in"))
      (node (ref "U5") (pin "6") (pinfunction "Vout_-_6") (pintype "power_in"))
      (node (ref "VR3") (pin "4") (pinfunction "GND_4") (pintype "power_in"))
      (node (ref "Y2") (pin "3") (pinfunction "3_3") (pintype "passive"))
      (node (ref "Y2") (pin "4") (pinfunction "4_4") (pintype "passive"))
    )
    (net (code "75") (name "GLV_VCC") (class "Default")
      (node (ref "C12") (pin "2") (pinfunction "2_2") (pintype "passive"))
      (node (ref "C13") (pin "2") (pinfunction "2_2") (pintype "passive"))
      (node (ref "C21") (pin "2") (pinfunction "2_2") (pintype "passive"))
      (node (ref "C30") (pin "1") (pinfunction "1_1") (pintype "passive"))
      (node (ref "C5") (pin "1") (pinfunction "1_1") (pintype "passive"))
      (node (ref "C6") (pin "1") (pinfunction "1_1") (pintype "passive"))
      (node (ref "C8") (pin "2") (pinfunction "2_2") (pintype "passive"))
      (node (ref "C9") (pin "2") (pinfunction "2_2") (pintype "passive"))
      (node (ref "D2") (pin "1") (pinfunction "A_1") (pintype "passive"))
      (node (ref "D3") (pin "1") (pinfunction "A_1") (pintype "passive"))
      (node (ref "D4") (pin "1") (pinfunction "A_1") (pintype "passive"))
      (node (ref "J3") (pin "2") (pinfunction "2_2") (pintype "passive"))
      (node (ref "J4") (pin "8") (pinfunction "8_8") (pintype "passive"))
      (node (ref "L1") (pin "1") (pinfunction "1_1") (pintype "passive"))
      (node (ref "R10") (pin "2") (pinfunction "2_2") (pintype "passive"))
      (node (ref "R30") (pin "1") (pinfunction "1_1") (pintype "passive"))
      (node (ref "R33") (pin "1") (pinfunction "1_1") (pintype "passive"))
      (node (ref "R47") (pin "1") (pinfunction "1_1") (pintype "passive"))
      (node (ref "R51") (pin "1") (pinfunction "1_1") (pintype "passive"))
      (node (ref "U1") (pin "4") (pinfunction "VCC_4") (pintype "power_in"))
      (node (ref "U2") (pin "18") (pinfunction "VDD_18") (pintype "power_in"))
      (node (ref "U3") (pin "3") (pinfunction "VCC_3") (pintype "passive"))
      (node (ref "U4") (pin "3") (pinfunction "VCC_3") (pintype "passive"))
      (node (ref "U5") (pin "8") (pinfunction "VDD2_8") (pintype "power_in"))
      (node (ref "VR3") (pin "3") (pinfunction "OUT_3") (pintype "power_in"))
    )
    (net (code "76") (name "Net-(U3-RXD)") (class "Default")
      (node (ref "R11") (pin "1") (pinfunction "1_1") (pintype "passive"))
      (node (ref "U3") (pin "4") (pinfunction "RXD_4") (pintype "input"))
    )
    (net (code "77") (name "Net-(U3-TXD)") (class "Default")
      (node (ref "R12") (pin "2") (pinfunction "2_2") (pintype "passive"))
      (node (ref "U3") (pin "1") (pinfunction "TXD_1") (pintype "output"))
    )
    (net (code "78") (name "unconnected-(J2-Pad6)") (class "Default")
      (node (ref "J2") (pin "6") (pinfunction "6_6") (pintype "passive"))
    )
    (net (code "79") (name "unconnected-(U1-PB2-Pad16)") (class "Default")
      (node (ref "U1") (pin "16") (pinfunction "PB2_16") (pintype "output"))
    )
    (net (code "80") (name "unconnected-(U1-PC0-Pad30)") (class "Default")
      (node (ref "U1") (pin "30") (pinfunction "PC0_30") (pintype "passive"))
    )
  )
)
